# SimpleControllboard.net
KiCad netlist of a schematic drawn in EAGLE
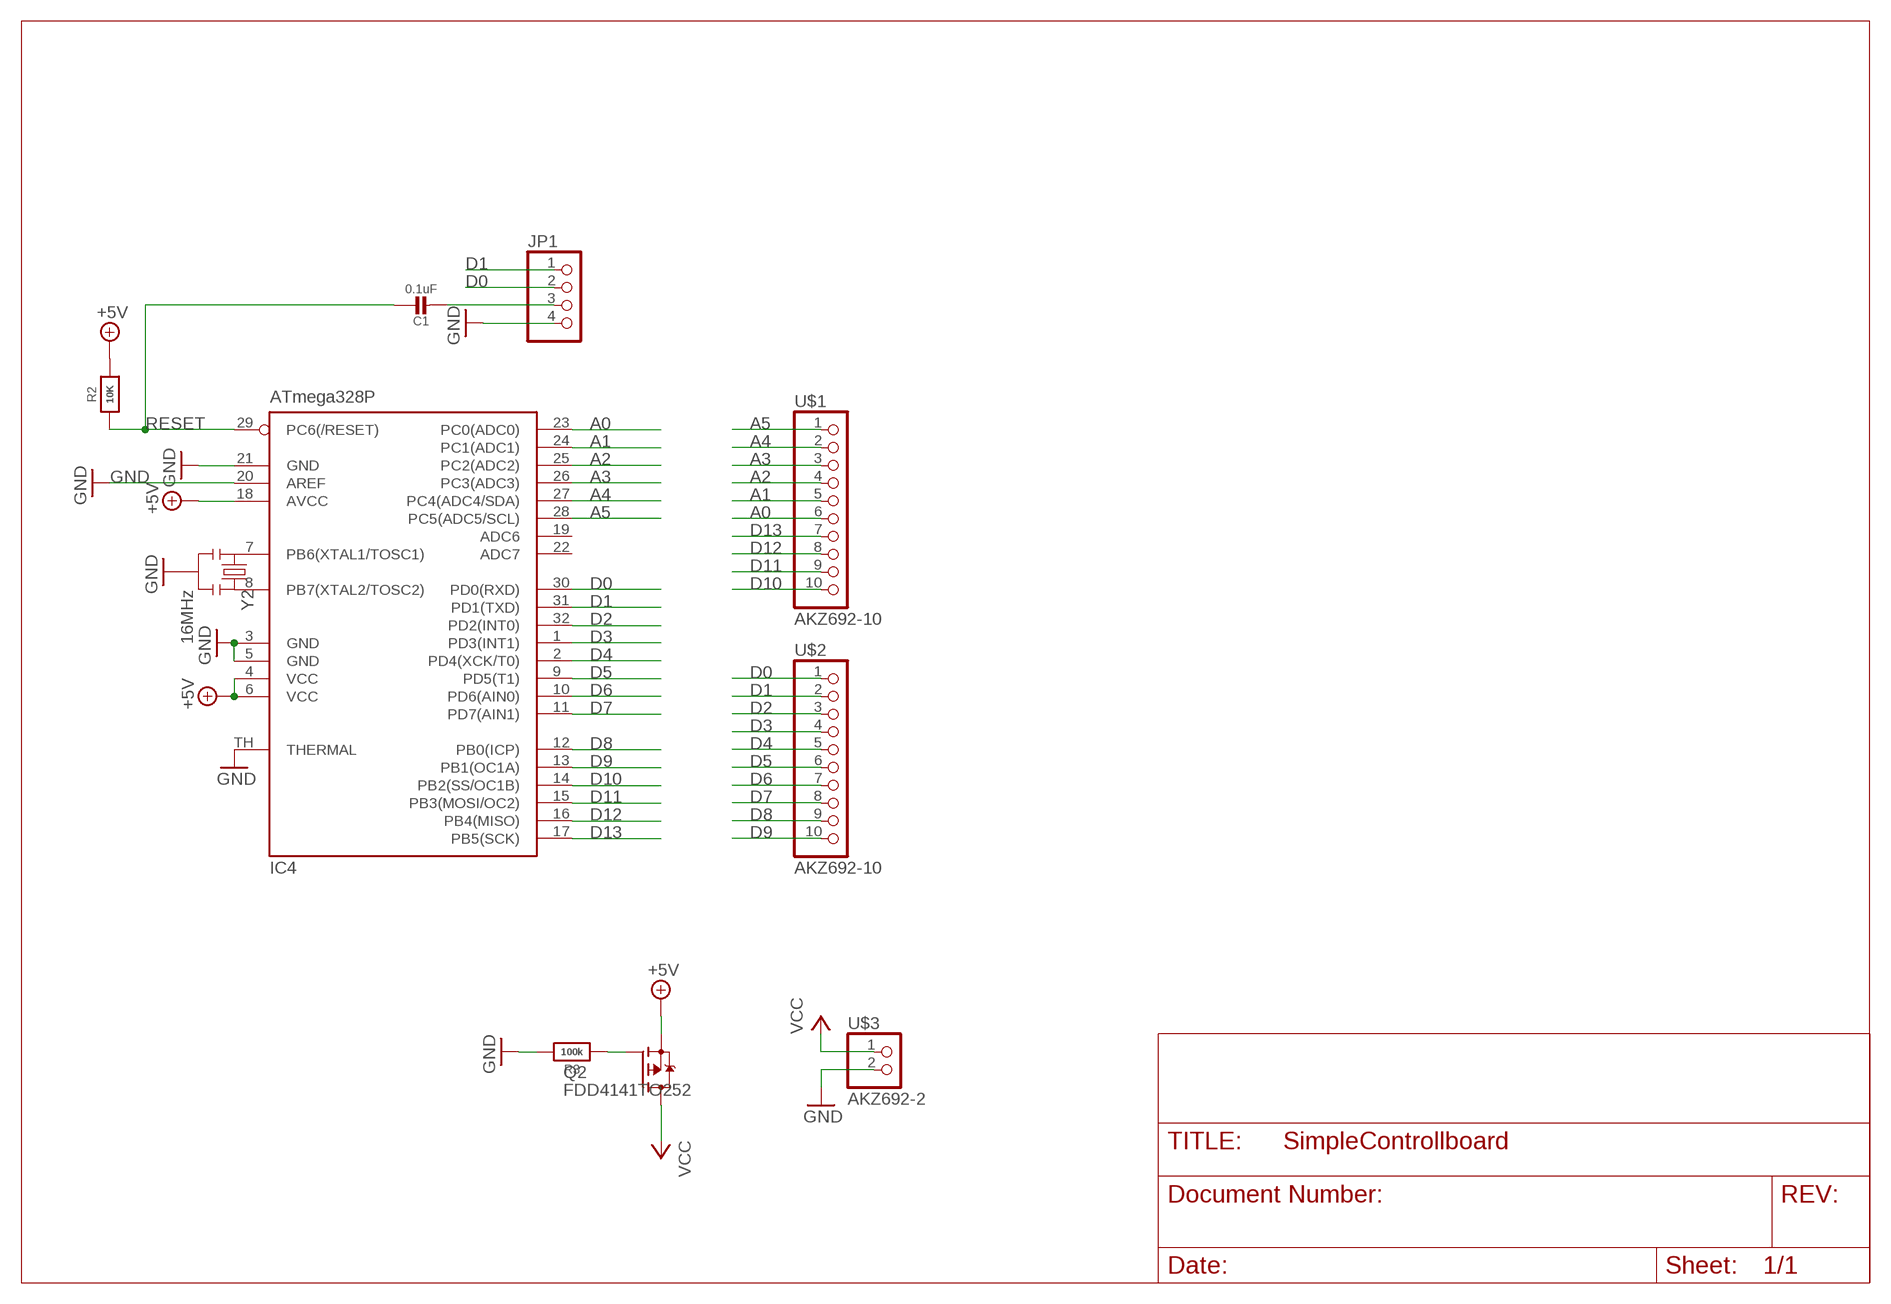
[diagram p0: schematic, sheet 1]

(export (version "E")
  (design (tool "Eeschema 10.0.6"))
  (components
    (comp (ref "C1")
      (value "0.1uF")
      (footprint "eagle-import:0805-NO")
      (libsource (lib "eagle-import") (part "CAP_CERAMIC0805-NOOUTLINE"))
    )
    (comp (ref "IC4")
      (value "ATmega328P")
      (footprint "eagle-import:MLF32-TH")
      (fields (field (name "MPN") "ATMEGA88PA-MU"))
      (libsource (lib "eagle-import") (part "MEGA8-MI"))
    )
    (comp (ref "JP1")
      (value "PINHD-1X4")
      (footprint "eagle-import:1X04")
      (libsource (lib "eagle-import") (part "PINHD-1X4"))
    )
    (comp (ref "Q2")
      (value "FDD4141TO252")
      (footprint "eagle-import:TO252")
      (libsource (lib "eagle-import") (part "FDD4141TO252"))
    )
    (comp (ref "R2")
      (value "10K")
      (footprint "eagle-import:0805-NO")
      (libsource (lib "eagle-import") (part "RESISTOR0805_NOOUTLINE"))
    )
    (comp (ref "R3")
      (value "100k")
      (footprint "eagle-import:0805-NO")
      (libsource (lib "eagle-import") (part "RESISTOR0805_NOOUTLINE"))
    )
    (comp (ref "U$1")
      (value "AKZ692-10")
      (footprint "eagle-import:1X10")
      (libsource (lib "eagle-import") (part "AKZ692-10"))
    )
    (comp (ref "U$2")
      (value "AKZ692-10")
      (footprint "eagle-import:1X10")
      (libsource (lib "eagle-import") (part "AKZ692-10"))
    )
    (comp (ref "U$3")
      (value "AKZ692-2")
      (footprint "eagle-import:1X2")
      (libsource (lib "eagle-import") (part "AKZ692-2"))
    )
    (comp (ref "Y2")
      (value "16MHz")
      (footprint "eagle-import:RESONATOR-SMD")
      (libsource (lib "eagle-import") (part "RESONATORSMD"))
    )
  )
  (nets
    (net (code "1") (name "+5V") (class "Default")
      (node (ref "IC4") (pin "18") (pinfunction "AVCC_18") (pintype "power_in"))
      (node (ref "IC4") (pin "4") (pinfunction "VCC_4") (pintype "power_in"))
      (node (ref "IC4") (pin "6") (pinfunction "VCC_6") (pintype "power_in"))
      (node (ref "Q2") (pin "2") (pinfunction "S_2") (pintype "passive"))
      (node (ref "R2") (pin "2") (pinfunction "2_2") (pintype "passive"))
    )
    (net (code "2") (name "/A0") (class "Default")
      (node (ref "IC4") (pin "23") (pinfunction "PC0(ADC0)_23") (pintype "bidirectional"))
      (node (ref "U$1") (pin "6") (pinfunction "6_6") (pintype "passive"))
    )
    (net (code "3") (name "/A1") (class "Default")
      (node (ref "IC4") (pin "24") (pinfunction "PC1(ADC1)_24") (pintype "bidirectional"))
      (node (ref "U$1") (pin "5") (pinfunction "5_5") (pintype "passive"))
    )
    (net (code "4") (name "/A2") (class "Default")
      (node (ref "IC4") (pin "25") (pinfunction "PC2(ADC2)_25") (pintype "bidirectional"))
      (node (ref "U$1") (pin "4") (pinfunction "4_4") (pintype "passive"))
    )
    (net (code "5") (name "/A3") (class "Default")
      (node (ref "IC4") (pin "26") (pinfunction "PC3(ADC3)_26") (pintype "bidirectional"))
      (node (ref "U$1") (pin "3") (pinfunction "3_3") (pintype "passive"))
    )
    (net (code "6") (name "/A4") (class "Default")
      (node (ref "IC4") (pin "27") (pinfunction "PC4(ADC4/SDA)_27") (pintype "bidirectional"))
      (node (ref "U$1") (pin "2") (pinfunction "2_2") (pintype "passive"))
    )
    (net (code "7") (name "/A5") (class "Default")
      (node (ref "IC4") (pin "28") (pinfunction "PC5(ADC5/SCL)_28") (pintype "bidirectional"))
      (node (ref "U$1") (pin "1") (pinfunction "1_1") (pintype "passive"))
    )
    (net (code "8") (name "/D0") (class "Default")
      (node (ref "IC4") (pin "30") (pinfunction "PD0(RXD)_30") (pintype "bidirectional"))
      (node (ref "JP1") (pin "2") (pinfunction "2_2") (pintype "passive"))
      (node (ref "U$2") (pin "1") (pinfunction "1_1") (pintype "passive"))
    )
    (net (code "9") (name "/D1") (class "Default")
      (node (ref "IC4") (pin "31") (pinfunction "PD1(TXD)_31") (pintype "bidirectional"))
      (node (ref "JP1") (pin "1") (pinfunction "1_1") (pintype "passive"))
      (node (ref "U$2") (pin "2") (pinfunction "2_2") (pintype "passive"))
    )
    (net (code "10") (name "/D2") (class "Default")
      (node (ref "IC4") (pin "32") (pinfunction "PD2(INT0)_32") (pintype "bidirectional"))
      (node (ref "U$2") (pin "3") (pinfunction "3_3") (pintype "passive"))
    )
    (net (code "11") (name "/D3") (class "Default")
      (node (ref "IC4") (pin "1") (pinfunction "PD3(INT1)_1") (pintype "bidirectional"))
      (node (ref "U$2") (pin "4") (pinfunction "4_4") (pintype "passive"))
    )
    (net (code "12") (name "/D4") (class "Default")
      (node (ref "IC4") (pin "2") (pinfunction "PD4(XCK/T0)_2") (pintype "bidirectional"))
      (node (ref "U$2") (pin "5") (pinfunction "5_5") (pintype "passive"))
    )
    (net (code "13") (name "/D5") (class "Default")
      (node (ref "IC4") (pin "9") (pinfunction "PD5(T1)_9") (pintype "bidirectional"))
      (node (ref "U$2") (pin "6") (pinfunction "6_6") (pintype "passive"))
    )
    (net (code "14") (name "/D6") (class "Default")
      (node (ref "IC4") (pin "10") (pinfunction "PD6(AIN0)_10") (pintype "bidirectional"))
      (node (ref "U$2") (pin "7") (pinfunction "7_7") (pintype "passive"))
    )
    (net (code "15") (name "/D7") (class "Default")
      (node (ref "IC4") (pin "11") (pinfunction "PD7(AIN1)_11") (pintype "bidirectional"))
      (node (ref "U$2") (pin "8") (pinfunction "8_8") (pintype "passive"))
    )
    (net (code "16") (name "/D8") (class "Default")
      (node (ref "IC4") (pin "12") (pinfunction "PB0(ICP)_12") (pintype "bidirectional"))
      (node (ref "U$2") (pin "9") (pinfunction "9_9") (pintype "passive"))
    )
    (net (code "17") (name "/D9") (class "Default")
      (node (ref "IC4") (pin "13") (pinfunction "PB1(OC1A)_13") (pintype "bidirectional"))
      (node (ref "U$2") (pin "10") (pinfunction "10_10") (pintype "passive"))
    )
    (net (code "18") (name "/D10") (class "Default")
      (node (ref "IC4") (pin "14") (pinfunction "PB2(SS/OC1B)_14") (pintype "bidirectional"))
      (node (ref "U$1") (pin "10") (pinfunction "10_10") (pintype "passive"))
    )
    (net (code "19") (name "/D11") (class "Default")
      (node (ref "IC4") (pin "15") (pinfunction "PB3(MOSI/OC2)_15") (pintype "bidirectional"))
      (node (ref "U$1") (pin "9") (pinfunction "9_9") (pintype "passive"))
    )
    (net (code "20") (name "/D12") (class "Default")
      (node (ref "IC4") (pin "16") (pinfunction "PB4(MISO)_16") (pintype "bidirectional"))
      (node (ref "U$1") (pin "8") (pinfunction "8_8") (pintype "passive"))
    )
    (net (code "21") (name "/D13") (class "Default")
      (node (ref "IC4") (pin "17") (pinfunction "PB5(SCK)_17") (pintype "bidirectional"))
      (node (ref "U$1") (pin "7") (pinfunction "7_7") (pintype "passive"))
    )
    (net (code "22") (name "/RESET") (class "Default")
      (node (ref "C1") (pin "1") (pinfunction "1_1") (pintype "passive"))
      (node (ref "IC4") (pin "29") (pinfunction "PC6(/RESET)_29") (pintype "bidirectional"))
      (node (ref "R2") (pin "1") (pinfunction "1_1") (pintype "passive"))
    )
    (net (code "23") (name "GND") (class "Default")
      (node (ref "IC4") (pin "20") (pinfunction "AREF_20") (pintype "passive"))
      (node (ref "IC4") (pin "21") (pinfunction "GND_21") (pintype "power_in"))
      (node (ref "IC4") (pin "3") (pinfunction "GND_3") (pintype "power_in"))
      (node (ref "IC4") (pin "5") (pinfunction "GND_5") (pintype "power_in"))
      (node (ref "IC4") (pin "TH") (pinfunction "THERMAL_TH") (pintype "passive"))
      (node (ref "JP1") (pin "4") (pinfunction "4_4") (pintype "passive"))
      (node (ref "R3") (pin "2") (pinfunction "2_2") (pintype "passive"))
      (node (ref "U$3") (pin "2") (pinfunction "2_2") (pintype "passive"))
      (node (ref "Y2") (pin "2") (pinfunction "2_2") (pintype "passive"))
    )
    (net (code "24") (name "Net-(C1-Pad2)") (class "Default")
      (node (ref "C1") (pin "2") (pinfunction "2_2") (pintype "passive"))
      (node (ref "JP1") (pin "3") (pinfunction "3_3") (pintype "passive"))
    )
    (net (code "25") (name "Net-(IC4-PB6(XTAL1{slash}TOSC1))") (class "Default")
      (node (ref "IC4") (pin "7") (pinfunction "PB6(XTAL1/TOSC1)_7") (pintype "bidirectional"))
      (node (ref "Y2") (pin "1") (pinfunction "1_1") (pintype "passive"))
    )
    (net (code "26") (name "Net-(IC4-PB7(XTAL2{slash}TOSC2))") (class "Default")
      (node (ref "IC4") (pin "8") (pinfunction "PB7(XTAL2/TOSC2)_8") (pintype "bidirectional"))
      (node (ref "Y2") (pin "3") (pinfunction "3_3") (pintype "passive"))
    )
    (net (code "27") (name "Net-(Q2-G)") (class "Default")
      (node (ref "Q2") (pin "1") (pinfunction "G_1") (pintype "passive"))
      (node (ref "R3") (pin "1") (pinfunction "1_1") (pintype "passive"))
    )
    (net (code "28") (name "VCC") (class "Default")
      (node (ref "Q2") (pin "3") (pinfunction "D_3") (pintype "passive"))
      (node (ref "U$3") (pin "1") (pinfunction "1_1") (pintype "passive"))
    )
    (net (code "29") (name "unconnected-(IC4-ADC6-Pad19)") (class "Default")
      (node (ref "IC4") (pin "19") (pinfunction "ADC6_19") (pintype "bidirectional"))
    )
    (net (code "30") (name "unconnected-(IC4-ADC7-Pad22)") (class "Default")
      (node (ref "IC4") (pin "22") (pinfunction "ADC7_22") (pintype "bidirectional"))
    )
  )
)
